# 3V3_REG.net
KiCad netlist of a schematic drawn in Altium Designer
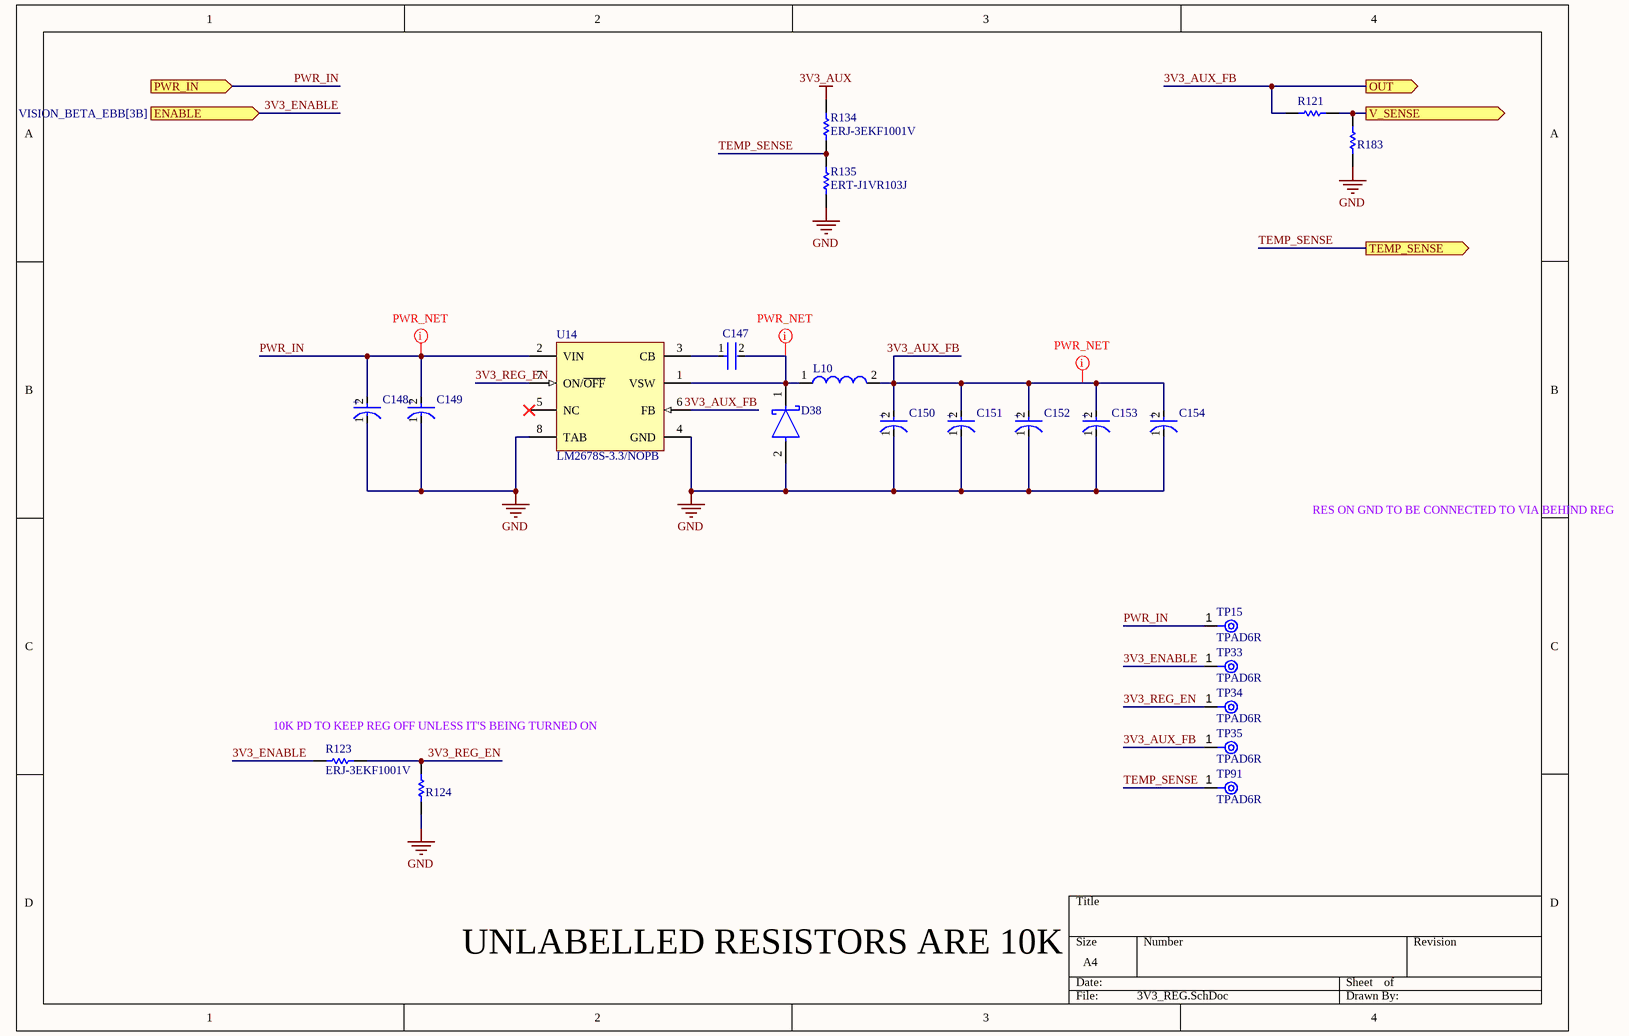
[diagram p0: 3V3_REG.SchDoc]

(export (version "E")
  (design (tool "Eeschema 10.0.6"))
  (components
    (comp (ref "C147")
      (value "C0805C103J5RACTU")
      (footprint "FP-C0805C-DN-MFG")
      (description "CAP CER 10000PF 50V X7R 0805")
      (fields
        (field (name "MANUFACTURER") "KEMET")
        (field (name "OCTOPART") "https://octopart.com/c0805c103j5ractu-kemet-133473")
      )
      (libsource (lib "Altium Content Vault") (part "b4654b650e69147ec39a6b967a45e02"))
    )
    (comp (ref "C148")
      (value "EEHZA1V680XP")
      (footprint "FP-EEH-D8-MFG")
      (description "Conductive Polymer Hybrid Aluminum Electrolytic Capacitors 68uF ±20% 35V RADIAL SMT 6.3x7.7mm")
      (fields (field (name "VOLTAGE") "35V") (field (name "TOLERANCE") "20%"))
      (libsource (lib "Altium Content Vault") (part "a00bbbee19879c290e62620ae7e47b1"))
    )
    (comp (ref "C149")
      (value "EEHZA1V680XP")
      (footprint "FP-EEH-D8-MFG")
      (description "Conductive Polymer Hybrid Aluminum Electrolytic Capacitors 68uF ±20% 35V RADIAL SMT 6.3x7.7mm")
      (fields (field (name "VOLTAGE") "35V") (field (name "TOLERANCE") "20%"))
      (libsource (lib "Altium Content Vault") (part "a00bbbee19879c290e62620ae7e47b1"))
    )
    (comp (ref "C150")
      (value "16SVPC120M")
      (footprint "FP-OS-CON-SMT-E7-MFG")
      (description "Conductive Polymer Aluminum Solid Capacitors (OS-CON) 120uF ±20% 16V RADIAL SMT 8x6.9mm")
      (fields (field (name "VOLTAGE") "16V") (field (name "TOLERANCE") "20%"))
      (libsource (lib "Altium Content Vault") (part "cf48714ba7e38822c1575c7ec0b6d1f"))
    )
    (comp (ref "C151")
      (value "16SVPC120M")
      (footprint "FP-OS-CON-SMT-E7-MFG")
      (description "Conductive Polymer Aluminum Solid Capacitors (OS-CON) 120uF ±20% 16V RADIAL SMT 8x6.9mm")
      (fields (field (name "VOLTAGE") "16V") (field (name "TOLERANCE") "20%"))
      (libsource (lib "Altium Content Vault") (part "cf48714ba7e38822c1575c7ec0b6d1f"))
    )
    (comp (ref "C152")
      (value "16SVPC120M")
      (footprint "FP-OS-CON-SMT-E7-MFG")
      (description "Conductive Polymer Aluminum Solid Capacitors (OS-CON) 120uF ±20% 16V RADIAL SMT 8x6.9mm")
      (fields (field (name "VOLTAGE") "16V") (field (name "TOLERANCE") "20%"))
      (libsource (lib "Altium Content Vault") (part "cf48714ba7e38822c1575c7ec0b6d1f"))
    )
    (comp (ref "C153")
      (value "16SVPC120M")
      (footprint "FP-OS-CON-SMT-E7-MFG")
      (description "Conductive Polymer Aluminum Solid Capacitors (OS-CON) 120uF ±20% 16V RADIAL SMT 8x6.9mm")
      (fields (field (name "VOLTAGE") "16V") (field (name "TOLERANCE") "20%"))
      (libsource (lib "Altium Content Vault") (part "cf48714ba7e38822c1575c7ec0b6d1f"))
    )
    (comp (ref "C154")
      (value "16SVPC120M")
      (footprint "FP-OS-CON-SMT-E7-MFG")
      (description "Conductive Polymer Aluminum Solid Capacitors (OS-CON) 120uF ±20% 16V RADIAL SMT 8x6.9mm")
      (fields (field (name "VOLTAGE") "16V") (field (name "TOLERANCE") "20%"))
      (libsource (lib "Altium Content Vault") (part "cf48714ba7e38822c1575c7ec0b6d1f"))
    )
    (comp (ref "D38")
      (value "B540C-13-F")
      (footprint "FP-SMC-MFG")
      (description "DIODE SCHOTTKY 40V 5A SMC")
      (fields
        (field (name "OCTOPART") "https://octopart.com/b540c-13-f-diodes+inc.-325873")
        (field (name "MANUFACTURER") "Diodes Inc.")
      )
      (libsource (lib "Altium Content Vault") (part "1d6ec82d83fb6aee721767c19dac4b9"))
    )
    (comp (ref "L10")
      (value "74477110")
      (footprint "WE-PD-L")
      (description "SMD-Shielded Power Inductor WE-PD, L = 10.0 µH")
      (libsource (lib "Altium Content Vault") (part "PAS-IND-INDUCTOR-2"))
    )
    (comp (ref "R121")
      (value "ERJ3EKF1002V")
      (footprint "RESC1609X55X30LL15T15")
      (description "Chip Resistor, 10 KOhm, +/- 1%, 0.1 W, -55 to 155 degC, 0603 (1608 Metric), RoHS, Tape and Reel")
      (fields (field (name "TOLERANCE") "1%") (field (name "MANUFACTURER") "Panasonic"))
      (libsource (lib "Altium Content Vault") (part "RES-2"))
    )
    (comp (ref "R123")
      (value "ERJ-3EKF1001V")
      (footprint "RESC1608X55X30LL15T15")
      (fields (field (name "MANUFACTURER") "Panasonic"))
      (libsource (lib "Altium Content Vault") (part "RES"))
    )
    (comp (ref "R124")
      (value "ERJ3EKF1002V")
      (footprint "RESC1609X55X30LL15T15")
      (description "Chip Resistor, 10 KOhm, +/- 1%, 0.1 W, -55 to 155 degC, 0603 (1608 Metric), RoHS, Tape and Reel")
      (fields (field (name "TOLERANCE") "1%") (field (name "MANUFACTURER") "Panasonic"))
      (libsource (lib "Altium Content Vault") (part "RES-2"))
    )
    (comp (ref "R134")
      (value "ERJ-3EKF1001V")
      (footprint "RESC1608X55X30LL15T15")
      (fields (field (name "MANUFACTURER") "Panasonic"))
      (libsource (lib "Altium Content Vault") (part "RES"))
    )
    (comp (ref "R135")
      (value "ERT-J1VR103J")
      (footprint "RESC1608X90X30ML15T20")
      (fields (field (name "MANUFACTURER") "Panasonic"))
      (libsource (lib "Altium Content Vault") (part "RES"))
    )
    (comp (ref "R183")
      (value "ERJ3EKF1002V")
      (footprint "RESC1609X55X30LL15T15")
      (description "Chip Resistor, 10 KOhm, +/- 1%, 0.1 W, -55 to 155 degC, 0603 (1608 Metric), RoHS, Tape and Reel")
      (fields (field (name "TOLERANCE") "1%") (field (name "MANUFACTURER") "Panasonic"))
      (libsource (lib "Altium Content Vault") (part "RES-2"))
    )
    (comp (ref "TP15")
      (value "TPAD6R")
      (footprint "New footprint 1")
      (description "Test Point .6mm")
      (libsource (lib "Space Concordia") (part "TP"))
    )
    (comp (ref "TP33")
      (value "TPAD6R")
      (footprint "New footprint 1")
      (description "Test Point .6mm")
      (libsource (lib "Space Concordia") (part "TP"))
    )
    (comp (ref "TP34")
      (value "TPAD6R")
      (footprint "New footprint 1")
      (description "Test Point .6mm")
      (libsource (lib "Space Concordia") (part "TP"))
    )
    (comp (ref "TP35")
      (value "TPAD6R")
      (footprint "New footprint 1")
      (description "Test Point .6mm")
      (libsource (lib "Space Concordia") (part "TP"))
    )
    (comp (ref "TP91")
      (value "TPAD6R")
      (footprint "New footprint 1")
      (description "Test Point .6mm")
      (libsource (lib "Space Concordia") (part "TP"))
    )
    (comp (ref "U14")
      (value "LM2678S-3.3/NOPB")
      (footprint "KTW0007B_N")
      (description "SIMPLE SWITCHER® High Efficiency 5A Step-Down Voltage Regulator, 7-pin TO-263, Pb-Free")
      (fields (field (name "MANUFACTURER") "Texas Instruments"))
      (libsource (lib "Altium Content Vault") (part "PM-REG-LM2678S"))
    )
  )
  (nets
    (net (code "1") (name "/3V3_AUX_FB") (class "Default")
      (node (ref "C150") (pin "2") (pinfunction "A_2") (pintype "passive"))
      (node (ref "C151") (pin "2") (pinfunction "A_2") (pintype "passive"))
      (node (ref "C152") (pin "2") (pinfunction "A_2") (pintype "passive"))
      (node (ref "C153") (pin "2") (pinfunction "A_2") (pintype "passive"))
      (node (ref "C154") (pin "2") (pinfunction "A_2") (pintype "passive"))
      (node (ref "L10") (pin "2") (pinfunction "2_2") (pintype "passive"))
      (node (ref "R121") (pin "1") (pinfunction "1_1") (pintype "passive"))
      (node (ref "TP35") (pin "1") (pinfunction "TP_1") (pintype "passive"))
      (node (ref "U14") (pin "6") (pinfunction "FB_6") (pintype "input"))
    )
    (net (code "2") (name "/3V3_ENABLE") (class "Default")
      (node (ref "R123") (pin "1") (pinfunction "1_1") (pintype "passive"))
      (node (ref "TP33") (pin "1") (pinfunction "TP_1") (pintype "passive"))
    )
    (net (code "3") (name "/3V3_REG_EN") (class "Default")
      (node (ref "R123") (pin "2") (pinfunction "2_2") (pintype "passive"))
      (node (ref "R124") (pin "2") (pinfunction "2_2") (pintype "passive"))
      (node (ref "TP34") (pin "1") (pinfunction "TP_1") (pintype "passive"))
      (node (ref "U14") (pin "7") (pinfunction "ON/~{OFF}_7") (pintype "input"))
    )
    (net (code "4") (name "/PWR_IN") (class "Default")
      (node (ref "C148") (pin "2") (pinfunction "A_2") (pintype "passive"))
      (node (ref "C149") (pin "2") (pinfunction "A_2") (pintype "passive"))
      (node (ref "TP15") (pin "1") (pinfunction "TP_1") (pintype "passive"))
      (node (ref "U14") (pin "2") (pinfunction "VIN_2") (pintype "power_in"))
    )
    (net (code "5") (name "/TEMP_SENSE") (class "Default")
      (node (ref "R134") (pin "1") (pinfunction "1_1") (pintype "passive"))
      (node (ref "R135") (pin "2") (pinfunction "2_2") (pintype "passive"))
      (node (ref "TP91") (pin "1") (pinfunction "TP_1") (pintype "passive"))
    )
    (net (code "6") (name "/V_SENSE") (class "Default")
      (node (ref "R121") (pin "2") (pinfunction "2_2") (pintype "passive"))
      (node (ref "R183") (pin "2") (pinfunction "2_2") (pintype "passive"))
    )
    (net (code "7") (name "3V3_AUX") (class "Default")
      (node (ref "R134") (pin "2") (pinfunction "2_2") (pintype "passive"))
    )
    (net (code "8") (name "GND") (class "Default")
      (node (ref "C148") (pin "1") (pinfunction "C_1") (pintype "passive"))
      (node (ref "C149") (pin "1") (pinfunction "C_1") (pintype "passive"))
      (node (ref "C150") (pin "1") (pinfunction "C_1") (pintype "passive"))
      (node (ref "C151") (pin "1") (pinfunction "C_1") (pintype "passive"))
      (node (ref "C152") (pin "1") (pinfunction "C_1") (pintype "passive"))
      (node (ref "C153") (pin "1") (pinfunction "C_1") (pintype "passive"))
      (node (ref "C154") (pin "1") (pinfunction "C_1") (pintype "passive"))
      (node (ref "D38") (pin "2") (pinfunction "A_2") (pintype "passive"))
      (node (ref "R124") (pin "1") (pinfunction "1_1") (pintype "passive"))
      (node (ref "R135") (pin "1") (pinfunction "1_1") (pintype "passive"))
      (node (ref "R183") (pin "1") (pinfunction "1_1") (pintype "passive"))
      (node (ref "U14") (pin "4") (pinfunction "GND_4") (pintype "power_in"))
      (node (ref "U14") (pin "8") (pinfunction "TAB_8") (pintype "power_in"))
    )
    (net (code "9") (name "Net-(D38-C)") (class "Default")
      (node (ref "C147") (pin "2") (pinfunction "2_2") (pintype "passive"))
      (node (ref "D38") (pin "1") (pinfunction "C_1") (pintype "passive"))
      (node (ref "L10") (pin "1") (pinfunction "1_1") (pintype "passive"))
      (node (ref "U14") (pin "1") (pinfunction "VSW_1") (pintype "power_in"))
    )
    (net (code "10") (name "Net-(U14-CB)") (class "Default")
      (node (ref "C147") (pin "1") (pinfunction "1_1") (pintype "passive"))
      (node (ref "U14") (pin "3") (pinfunction "CB_3") (pintype "passive"))
    )
    (net (code "11") (name "unconnected-(U14-NC-Pad5)") (class "Default")
      (node (ref "U14") (pin "5") (pinfunction "NC_5") (pintype "passive+no_connect"))
    )
  )
)
